# Power.net
KiCad netlist of a schematic drawn in Altium Designer
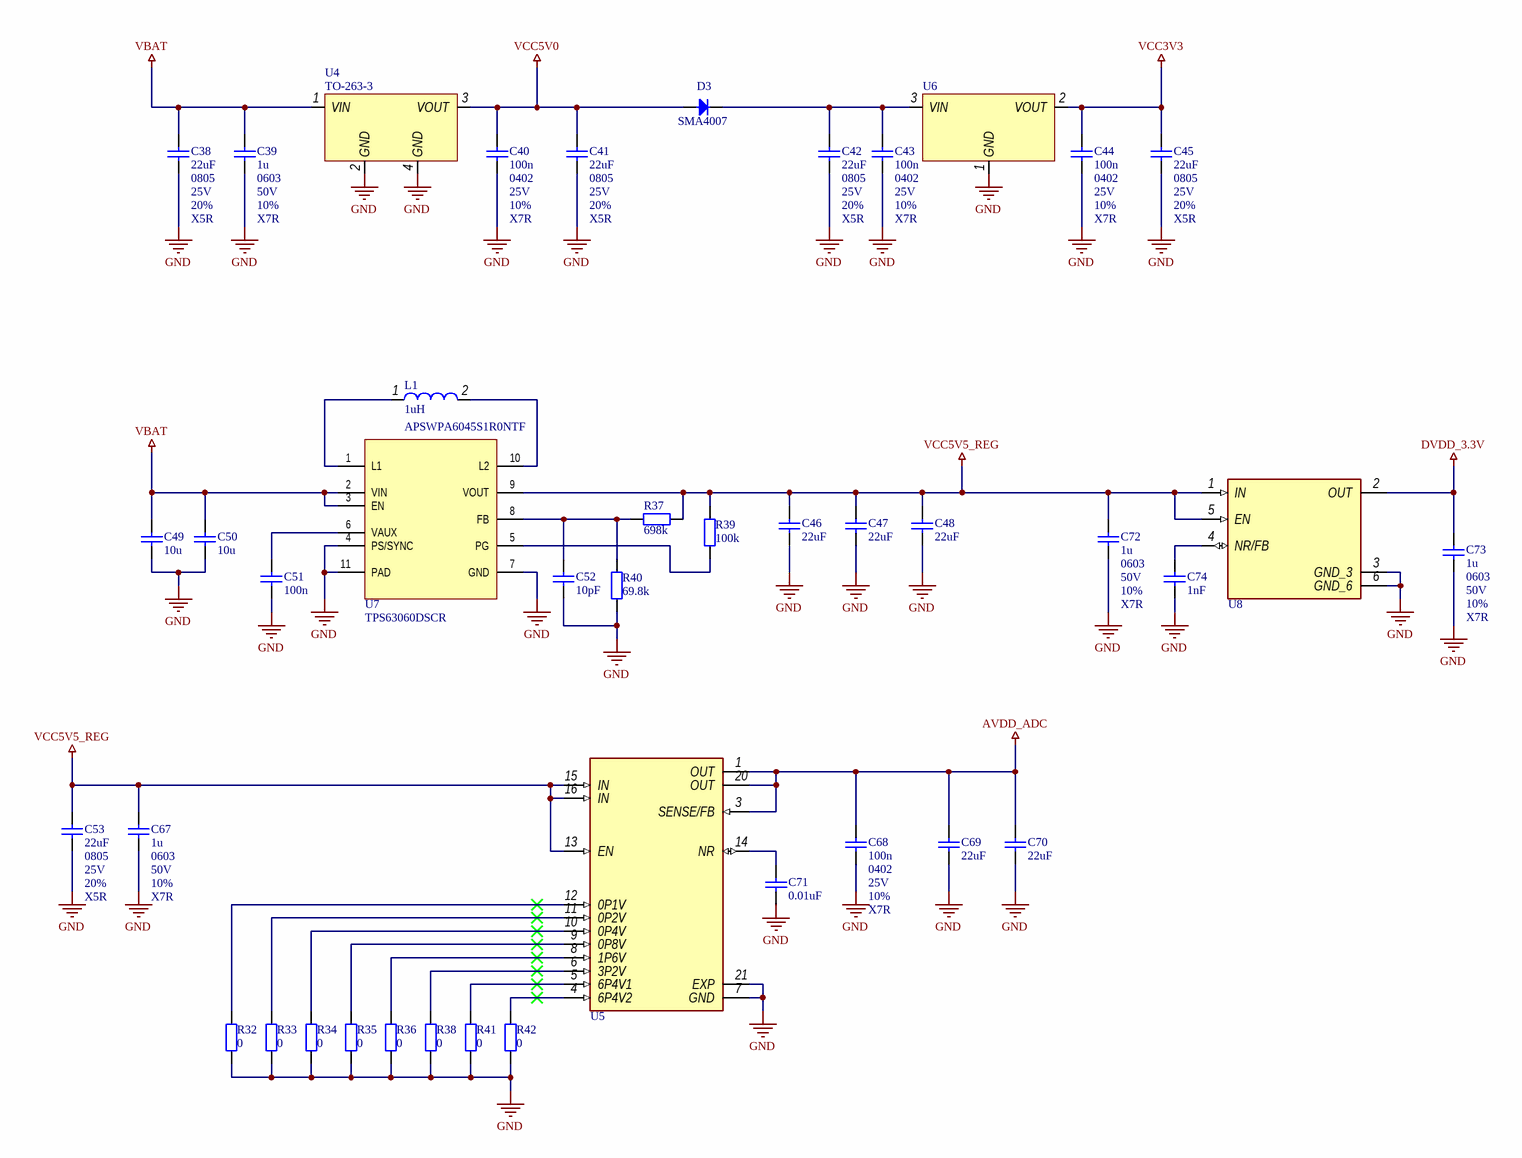
[diagram p0: Power.SchDoc]

(export (version "E")
  (design (tool "Eeschema 10.0.6"))
  (components
    (comp (ref "C38")
      (value "22uF")
      (footprint "CAPC2012X135N")
      (description "CAP CER 0805 22uF 25V X5R")
      (fields
        (field (name "PART NUMBER") "GRM21BR61E226ME44L")
        (field (name "DEVICE") "0805")
        (field (name "VOLTAGE") "25V")
        (field (name "TOLERANCE") "20%")
        (field (name "DIELECTRIC TYPE") "X5R")
        (field (name "MANUFACTURER") "Murata")
        (field (name "AUTHOR") "Arshanitsa D.")
      )
      (libsource (lib "tgl_lib_altium") (part "Capacitor - non polarized"))
    )
    (comp (ref "C39")
      (value "1u")
      (footprint "CAPC1608X85N")
      (description "CAP CER 0603 1u 50V X7R")
      (fields
        (field (name "PART NUMBER") "CC0603KRX7R9BB105")
        (field (name "DEVICE") "0603")
        (field (name "VOLTAGE") "50V")
        (field (name "TOLERANCE") "10%")
        (field (name "DIELECTRIC TYPE") "X7R")
        (field (name "MANUFACTURER") "Yageo")
        (field (name "AUTHOR") "Krepak V.")
      )
      (libsource (lib "tgl_lib_altium") (part "Capacitor - non polarized"))
    )
    (comp (ref "C40")
      (value "100n")
      (footprint "CAPC1005X55N")
      (description "CAP CER 0402 100n 25V X7R")
      (fields
        (field (name "PART NUMBER") "GRM155R71E104KE14D")
        (field (name "DEVICE") "0402")
        (field (name "VOLTAGE") "25V")
        (field (name "TOLERANCE") "10%")
        (field (name "DIELECTRIC TYPE") "X7R")
        (field (name "MANUFACTURER") "Murata")
        (field (name "AUTHOR") "Krepak V.")
      )
      (libsource (lib "tgl_lib_altium") (part "Capacitor - non polarized"))
    )
    (comp (ref "C41")
      (value "22uF")
      (footprint "CAPC2012X135N")
      (description "CAP CER 0805 22uF 25V X5R")
      (fields
        (field (name "PART NUMBER") "GRM21BR61E226ME44L")
        (field (name "DEVICE") "0805")
        (field (name "VOLTAGE") "25V")
        (field (name "TOLERANCE") "20%")
        (field (name "DIELECTRIC TYPE") "X5R")
        (field (name "MANUFACTURER") "Murata")
        (field (name "AUTHOR") "Arshanitsa D.")
      )
      (libsource (lib "tgl_lib_altium") (part "Capacitor - non polarized"))
    )
    (comp (ref "C42")
      (value "22uF")
      (footprint "CAPC2012X135N")
      (description "CAP CER 0805 22uF 25V X5R")
      (fields
        (field (name "PART NUMBER") "GRM21BR61E226ME44L")
        (field (name "DEVICE") "0805")
        (field (name "VOLTAGE") "25V")
        (field (name "TOLERANCE") "20%")
        (field (name "DIELECTRIC TYPE") "X5R")
        (field (name "MANUFACTURER") "Murata")
        (field (name "AUTHOR") "Arshanitsa D.")
      )
      (libsource (lib "tgl_lib_altium") (part "Capacitor - non polarized"))
    )
    (comp (ref "C43")
      (value "100n")
      (footprint "CAPC1005X55N")
      (description "CAP CER 0402 100n 25V X7R")
      (fields
        (field (name "PART NUMBER") "GRM155R71E104KE14D")
        (field (name "DEVICE") "0402")
        (field (name "VOLTAGE") "25V")
        (field (name "TOLERANCE") "10%")
        (field (name "DIELECTRIC TYPE") "X7R")
        (field (name "MANUFACTURER") "Murata")
        (field (name "AUTHOR") "Krepak V.")
      )
      (libsource (lib "tgl_lib_altium") (part "Capacitor - non polarized"))
    )
    (comp (ref "C44")
      (value "100n")
      (footprint "CAPC1005X55N")
      (description "CAP CER 0402 100n 25V X7R")
      (fields
        (field (name "PART NUMBER") "GRM155R71E104KE14D")
        (field (name "DEVICE") "0402")
        (field (name "VOLTAGE") "25V")
        (field (name "TOLERANCE") "10%")
        (field (name "DIELECTRIC TYPE") "X7R")
        (field (name "MANUFACTURER") "Murata")
        (field (name "AUTHOR") "Krepak V.")
      )
      (libsource (lib "tgl_lib_altium") (part "Capacitor - non polarized"))
    )
    (comp (ref "C45")
      (value "22uF")
      (footprint "CAPC2012X135N")
      (description "CAP CER 0805 22uF 25V X5R")
      (fields
        (field (name "PART NUMBER") "GRM21BR61E226ME44L")
        (field (name "DEVICE") "0805")
        (field (name "VOLTAGE") "25V")
        (field (name "TOLERANCE") "20%")
        (field (name "DIELECTRIC TYPE") "X5R")
        (field (name "MANUFACTURER") "Murata")
        (field (name "AUTHOR") "Arshanitsa D.")
      )
      (libsource (lib "tgl_lib_altium") (part "Capacitor - non polarized"))
    )
    (comp (ref "C46")
      (value "22uF")
      (footprint "CAPC2012X135N")
      (description "CAP CER 0805 22uF 25V X5R")
      (fields
        (field (name "PART NUMBER") "GRM21BR61E226ME44L")
        (field (name "VOLTAGE") "25V")
        (field (name "AUTHOR") "Arshanitsa D.")
      )
      (libsource (lib "tgl_lib_altium") (part "Capacitor - non polarized"))
    )
    (comp (ref "C47")
      (value "22uF")
      (footprint "CAPC2012X135N")
      (description "CAP CER 0805 22uF 25V X5R")
      (fields
        (field (name "PART NUMBER") "GRM21BR61E226ME44L")
        (field (name "VOLTAGE") "25V")
        (field (name "AUTHOR") "Arshanitsa D.")
      )
      (libsource (lib "tgl_lib_altium") (part "Capacitor - non polarized"))
    )
    (comp (ref "C48")
      (value "22uF")
      (footprint "CAPC2012X135N")
      (description "CAP CER 0805 22uF 25V X5R")
      (fields
        (field (name "PART NUMBER") "GRM21BR61E226ME44L")
        (field (name "VOLTAGE") "25V")
        (field (name "AUTHOR") "Arshanitsa D.")
      )
      (libsource (lib "tgl_lib_altium") (part "Capacitor - non polarized"))
    )
    (comp (ref "C49")
      (value "10u")
      (footprint "CAPC2012X135N")
      (description "CAP CER 0805 10u 25V X7R")
      (fields
        (field (name "PART NUMBER") "GRM21BZ71E106KE15L")
        (field (name "VOLTAGE") "25V")
        (field (name "AUTHOR") "Krepak V.")
      )
      (libsource (lib "tgl_lib_altium") (part "Capacitor - non polarized"))
    )
    (comp (ref "C50")
      (value "10u")
      (footprint "CAPC2012X135N")
      (description "CAP CER 0805 10u 25V X7R")
      (fields
        (field (name "PART NUMBER") "GRM21BZ71E106KE15L")
        (field (name "VOLTAGE") "25V")
        (field (name "AUTHOR") "Krepak V.")
      )
      (libsource (lib "tgl_lib_altium") (part "Capacitor - non polarized"))
    )
    (comp (ref "C51")
      (value "100n")
      (footprint "CAPC1005X55N")
      (description "CAP CER 0402 100n 25V X7R")
      (fields
        (field (name "PART NUMBER") "GRM155R71E104KE14D")
        (field (name "VOLTAGE") "25V")
        (field (name "AUTHOR") "Krepak V.")
      )
      (libsource (lib "tgl_lib_altium") (part "Capacitor - non polarized"))
    )
    (comp (ref "C52")
      (value "10pF")
      (footprint "CAPC1005X55N")
      (description "CAP CER 0402 10pF 50V NP0")
      (fields
        (field (name "PART NUMBER") "CC0402JRNPO9BN100")
        (field (name "VOLTAGE") "50V")
        (field (name "AUTHOR") "Krepak V.")
      )
      (libsource (lib "tgl_lib_altium") (part "Capacitor - non polarized"))
    )
    (comp (ref "C53")
      (value "22uF")
      (footprint "CAPC2012X135N")
      (description "CAP CER 0805 22uF 25V X5R")
      (fields
        (field (name "PART NUMBER") "GRM21BR61E226ME44L")
        (field (name "DEVICE") "0805")
        (field (name "VOLTAGE") "25V")
        (field (name "TOLERANCE") "20%")
        (field (name "DIELECTRIC TYPE") "X5R")
        (field (name "MANUFACTURER") "Murata")
        (field (name "AUTHOR") "Arshanitsa D.")
      )
      (libsource (lib "tgl_lib_altium") (part "Capacitor - non polarized"))
    )
    (comp (ref "C67")
      (value "1u")
      (footprint "CAPC1608X85N")
      (description "CAP CER 0603 1u 50V X7R")
      (fields
        (field (name "PART NUMBER") "CC0603KRX7R9BB105")
        (field (name "DEVICE") "0603")
        (field (name "VOLTAGE") "50V")
        (field (name "TOLERANCE") "10%")
        (field (name "DIELECTRIC TYPE") "X7R")
        (field (name "MANUFACTURER") "Yageo")
        (field (name "AUTHOR") "Krepak V.")
      )
      (libsource (lib "tgl_lib_altium") (part "Capacitor - non polarized"))
    )
    (comp (ref "C68")
      (value "100n")
      (footprint "CAPC1005X55N")
      (description "CAP CER 0402 100n 25V X7R")
      (fields
        (field (name "PART NUMBER") "GRM155R71E104KE14D")
        (field (name "DEVICE") "0402")
        (field (name "VOLTAGE") "25V")
        (field (name "TOLERANCE") "10%")
        (field (name "DIELECTRIC TYPE") "X7R")
        (field (name "MANUFACTURER") "Murata")
        (field (name "AUTHOR") "Krepak V.")
      )
      (libsource (lib "tgl_lib_altium") (part "Capacitor - non polarized"))
    )
    (comp (ref "C69")
      (value "22uF")
      (footprint "CAPC2012X135N")
      (description "CAP CER 0805 22uF 25V X5R")
      (fields
        (field (name "PART NUMBER") "GRM21BR61E226ME44L")
        (field (name "VOLTAGE") "25V")
        (field (name "AUTHOR") "Arshanitsa D.")
      )
      (libsource (lib "tgl_lib_altium") (part "Capacitor - non polarized"))
    )
    (comp (ref "C70")
      (value "22uF")
      (footprint "CAPC2012X135N")
      (description "CAP CER 0805 22uF 25V X5R")
      (fields
        (field (name "PART NUMBER") "GRM21BR61E226ME44L")
        (field (name "VOLTAGE") "25V")
        (field (name "AUTHOR") "Arshanitsa D.")
      )
      (libsource (lib "tgl_lib_altium") (part "Capacitor - non polarized"))
    )
    (comp (ref "C71")
      (value "0.01uF")
      (footprint "CAPC1005X55N")
      (description "CAP CER 0402 0.01uF 25V X7R")
      (fields
        (field (name "PART NUMBER") "CC0402KRX7R8BB103")
        (field (name "VOLTAGE") "25V")
        (field (name "AUTHOR") "Krepak V.")
      )
      (libsource (lib "tgl_lib_altium") (part "Capacitor - non polarized"))
    )
    (comp (ref "C72")
      (value "1u")
      (footprint "CAPC1608X85N")
      (description "CAP CER 0603 1u 50V X7R")
      (fields
        (field (name "PART NUMBER") "CC0603KRX7R9BB105")
        (field (name "DEVICE") "0603")
        (field (name "VOLTAGE") "50V")
        (field (name "TOLERANCE") "10%")
        (field (name "DIELECTRIC TYPE") "X7R")
        (field (name "MANUFACTURER") "Yageo")
        (field (name "AUTHOR") "Krepak V.")
      )
      (libsource (lib "tgl_lib_altium") (part "Capacitor - non polarized"))
    )
    (comp (ref "C73")
      (value "1u")
      (footprint "CAPC1608X85N")
      (description "CAP CER 0603 1u 50V X7R")
      (fields
        (field (name "PART NUMBER") "CC0603KRX7R9BB105")
        (field (name "DEVICE") "0603")
        (field (name "VOLTAGE") "50V")
        (field (name "TOLERANCE") "10%")
        (field (name "DIELECTRIC TYPE") "X7R")
        (field (name "MANUFACTURER") "Yageo")
        (field (name "AUTHOR") "Krepak V.")
      )
      (libsource (lib "tgl_lib_altium") (part "Capacitor - non polarized"))
    )
    (comp (ref "C74")
      (value "1nF")
      (footprint "CAPC1005X55N")
      (description "CAP CER 0402 1nF 50V NP0")
      (fields
        (field (name "PART NUMBER") "C1005C0G1H102JT000F")
        (field (name "VOLTAGE") "50V")
        (field (name "AUTHOR") "Krepak V.")
      )
      (libsource (lib "tgl_lib_altium") (part "Capacitor - non polarized"))
    )
    (comp (ref "D3")
      (value "SMA4007")
      (footprint "DO-214AC")
      (description "DIODE SMA4007")
      (fields (field (name "MANUFACTURER") "Wing Shing") (field (name "AUTHOR") "Krepak V."))
      (libsource (lib "tgl_lib_altium") (part "Diode"))
    )
    (comp (ref "L1")
      (value "1uH")
      (footprint "APSWPA6045")
      (description "IND APSWPA6045S1R0NTF 1uH ±30%")
      (fields
        (field (name "PART NUMBER") "APSWPA6045S1R0NTF")
        (field (name "TOLERANCE") "±30%")
        (field (name "MANUFACTURER") "APV")
        (field (name "AUTHOR") "Krepak V.")
      )
      (libsource (lib "tgl_lib_altium") (part "Ind"))
    )
    (comp (ref "R32")
      (value "0")
      (footprint "RESC1608X50N")
      (description "RES 0603 0 5%")
      (fields
        (field (name "PART NUMBER") "RC0603JR-070RL")
        (field (name "TOLERANCE") "5%")
        (field (name "AUTHOR") "Arshanitsa D.")
      )
      (libsource (lib "tgl_lib_altium") (part "Resistor1"))
    )
    (comp (ref "R33")
      (value "0")
      (footprint "RESC1608X50N")
      (description "RES 0603 0 5%")
      (fields
        (field (name "PART NUMBER") "RC0603JR-070RL")
        (field (name "TOLERANCE") "5%")
        (field (name "AUTHOR") "Arshanitsa D.")
      )
      (libsource (lib "tgl_lib_altium") (part "Resistor1"))
    )
    (comp (ref "R34")
      (value "0")
      (footprint "RESC1608X50N")
      (description "RES 0603 0 5%")
      (fields
        (field (name "PART NUMBER") "RC0603JR-070RL")
        (field (name "TOLERANCE") "5%")
        (field (name "AUTHOR") "Arshanitsa D.")
      )
      (libsource (lib "tgl_lib_altium") (part "Resistor1"))
    )
    (comp (ref "R35")
      (value "0")
      (footprint "RESC1608X50N")
      (description "RES 0603 0 5%")
      (fields
        (field (name "PART NUMBER") "RC0603JR-070RL")
        (field (name "TOLERANCE") "5%")
        (field (name "AUTHOR") "Arshanitsa D.")
      )
      (libsource (lib "tgl_lib_altium") (part "Resistor1"))
    )
    (comp (ref "R36")
      (value "0")
      (footprint "RESC1608X50N")
      (description "RES 0603 0 5%")
      (fields
        (field (name "PART NUMBER") "RC0603JR-070RL")
        (field (name "TOLERANCE") "5%")
        (field (name "AUTHOR") "Arshanitsa D.")
      )
      (libsource (lib "tgl_lib_altium") (part "Resistor1"))
    )
    (comp (ref "R37")
      (value "698k")
      (footprint "RESC1005X40N")
      (description "RES 0402 698k 1%")
      (fields
        (field (name "PART NUMBER") "RC0402FR-07698KL")
        (field (name "TOLERANCE") "1%")
        (field (name "AUTHOR") "Krepak V.")
      )
      (libsource (lib "") (part "Resistor1_1"))
    )
    (comp (ref "R38")
      (value "0")
      (footprint "RESC1608X50N")
      (description "RES 0603 0 5%")
      (fields
        (field (name "PART NUMBER") "RC0603JR-070RL")
        (field (name "TOLERANCE") "5%")
        (field (name "AUTHOR") "Arshanitsa D.")
      )
      (libsource (lib "tgl_lib_altium") (part "Resistor1"))
    )
    (comp (ref "R39")
      (value "100k")
      (footprint "RESC1005X40N")
      (description "RES 0402 100k 1%")
      (fields
        (field (name "PART NUMBER") "RC0402FR-07100KL")
        (field (name "TOLERANCE") "1%")
        (field (name "AUTHOR") "Krepak V.")
      )
      (libsource (lib "tgl_lib_altium") (part "Resistor1"))
    )
    (comp (ref "R40")
      (value "69.8k")
      (footprint "RESC1005X40N")
      (description "RES 0402 69.8k 1%")
      (fields
        (field (name "PART NUMBER") "RC0402FR-0769K8L")
        (field (name "TOLERANCE") "1%")
        (field (name "AUTHOR") "Krepak V.")
      )
      (libsource (lib "tgl_lib_altium") (part "Resistor1"))
    )
    (comp (ref "R41")
      (value "0")
      (footprint "RESC1608X50N")
      (description "RES 0603 0 5%")
      (fields
        (field (name "PART NUMBER") "RC0603JR-070RL")
        (field (name "TOLERANCE") "5%")
        (field (name "AUTHOR") "Arshanitsa D.")
      )
      (libsource (lib "tgl_lib_altium") (part "Resistor1"))
    )
    (comp (ref "R42")
      (value "0")
      (footprint "RESC1608X50N")
      (description "RES 0603 0 5%")
      (fields
        (field (name "PART NUMBER") "RC0603JR-070RL")
        (field (name "TOLERANCE") "5%")
        (field (name "AUTHOR") "Arshanitsa D.")
      )
      (libsource (lib "tgl_lib_altium") (part "Resistor1"))
    )
    (comp (ref "U4")
      (value "TO-263-3")
      (footprint "TO-263-3_L8.6-W10.2-P2.54-LS14.4-BR")
      (description "TO-263-3 Linear Voltage Regulators (LDO) ROHS")
      (fields
        (field (name "PART NUMBER") "LM7805S/TR")
        (field (name "Comment") "LM7805S")
        (field (name "AUTHOR") "Krepak V.")
      )
      (libsource (lib "tgl_lib_altium") (part "LM7805S"))
    )
    (comp (ref "U5")
      (value "TPS7A4700RGWR")
      (footprint "QFN65P500X500X100-21N")
      (description "1-A, 36-V, low-noise, high-PSRR, low-dropout voltage regulator with enable 20-VQFN -40 to 125")
      (fields (field (name "MF") "Texas Instruments") (field (name "AUTHOR") "Krepak V."))
      (libsource (lib "tgl_lib_altium") (part "TPS7A4700RGWR"))
    )
    (comp (ref "U6")
      (value "AMS1117-3.3")
      (footprint "SOT230P700-4BN")
      (libsource (lib "tgl_lib_altium") (part "AMS1117-3.3"))
    )
    (comp (ref "U7")
      (value "TPS63060DSCR")
      (footprint "WSON10")
      (description "Buck-boost type Adjustable 2.5V~8V 2A 2.5V~12V DFN-10(3x3) DC-DC Converters ROHS")
      (fields (field (name "MANUFACTURER") "Texas Instruments") (field (name "AUTHOR") "Krepak V."))
      (libsource (lib "tgl_lib_altium") (part "TPS63060"))
    )
    (comp (ref "U8")
      (value "TPS73733DCQR")
      (footprint "IC_TPS73733DCQR")
      (fields (field (name "AUTHOR") "Krepak V."))
      (libsource (lib "tgl_lib_altium") (part "TPS73733DCQR"))
    )
  )
  (nets
    (net (code "1") (name "AVDD_ADC") (class "Default")
      (node (ref "C68") (pin "2") (pinfunction "2_2") (pintype "passive"))
      (node (ref "C69") (pin "2") (pinfunction "2_2") (pintype "passive"))
      (node (ref "C70") (pin "2") (pinfunction "2_2") (pintype "passive"))
      (node (ref "U5") (pin "1") (pinfunction "OUT_1") (pintype "power_in"))
      (node (ref "U5") (pin "20") (pinfunction "OUT_20") (pintype "power_in"))
      (node (ref "U5") (pin "3") (pinfunction "SENSE/FB_3") (pintype "input"))
    )
    (net (code "2") (name "DVDD_3.3V") (class "Default")
      (node (ref "C73") (pin "2") (pinfunction "2_2") (pintype "passive"))
      (node (ref "U8") (pin "2") (pinfunction "OUT_2") (pintype "power_in"))
    )
    (net (code "3") (name "GND") (class "Default")
      (node (ref "C38") (pin "1") (pinfunction "1_1") (pintype "passive"))
      (node (ref "C39") (pin "1") (pinfunction "1_1") (pintype "passive"))
      (node (ref "C40") (pin "1") (pinfunction "1_1") (pintype "passive"))
      (node (ref "C41") (pin "1") (pinfunction "1_1") (pintype "passive"))
      (node (ref "C42") (pin "1") (pinfunction "1_1") (pintype "passive"))
      (node (ref "C43") (pin "1") (pinfunction "1_1") (pintype "passive"))
      (node (ref "C44") (pin "1") (pinfunction "1_1") (pintype "passive"))
      (node (ref "C45") (pin "1") (pinfunction "1_1") (pintype "passive"))
      (node (ref "C46") (pin "1") (pinfunction "1_1") (pintype "passive"))
      (node (ref "C47") (pin "1") (pinfunction "1_1") (pintype "passive"))
      (node (ref "C48") (pin "1") (pinfunction "1_1") (pintype "passive"))
      (node (ref "C49") (pin "1") (pinfunction "1_1") (pintype "passive"))
      (node (ref "C50") (pin "1") (pinfunction "1_1") (pintype "passive"))
      (node (ref "C51") (pin "1") (pinfunction "1_1") (pintype "passive"))
      (node (ref "C52") (pin "1") (pinfunction "1_1") (pintype "passive"))
      (node (ref "C53") (pin "1") (pinfunction "1_1") (pintype "passive"))
      (node (ref "C67") (pin "1") (pinfunction "1_1") (pintype "passive"))
      (node (ref "C68") (pin "1") (pinfunction "1_1") (pintype "passive"))
      (node (ref "C69") (pin "1") (pinfunction "1_1") (pintype "passive"))
      (node (ref "C70") (pin "1") (pinfunction "1_1") (pintype "passive"))
      (node (ref "C71") (pin "1") (pinfunction "1_1") (pintype "passive"))
      (node (ref "C72") (pin "1") (pinfunction "1_1") (pintype "passive"))
      (node (ref "C73") (pin "1") (pinfunction "1_1") (pintype "passive"))
      (node (ref "C74") (pin "1") (pinfunction "1_1") (pintype "passive"))
      (node (ref "R32") (pin "1") (pinfunction "1_1") (pintype "passive"))
      (node (ref "R33") (pin "1") (pinfunction "1_1") (pintype "passive"))
      (node (ref "R34") (pin "1") (pinfunction "1_1") (pintype "passive"))
      (node (ref "R35") (pin "1") (pinfunction "1_1") (pintype "passive"))
      (node (ref "R36") (pin "1") (pinfunction "1_1") (pintype "passive"))
      (node (ref "R38") (pin "1") (pinfunction "1_1") (pintype "passive"))
      (node (ref "R40") (pin "1") (pinfunction "1_1") (pintype "passive"))
      (node (ref "R41") (pin "1") (pinfunction "1_1") (pintype "passive"))
      (node (ref "R42") (pin "1") (pinfunction "1_1") (pintype "passive"))
      (node (ref "U4") (pin "2") (pinfunction "GND_2") (pintype "power_in"))
      (node (ref "U4") (pin "4") (pinfunction "GND_4") (pintype "power_in"))
      (node (ref "U5") (pin "21") (pinfunction "EXP_21") (pintype "power_in"))
      (node (ref "U5") (pin "7") (pinfunction "GND_7") (pintype "power_in"))
      (node (ref "U6") (pin "1") (pinfunction "GND_1") (pintype "power_in"))
      (node (ref "U7") (pin "11") (pinfunction "PAD_11") (pintype "power_in"))
      (node (ref "U7") (pin "4") (pinfunction "PS/SYNC_4") (pintype "passive"))
      (node (ref "U7") (pin "7") (pinfunction "GND_7") (pintype "power_in"))
      (node (ref "U8") (pin "3") (pinfunction "GND_3_3") (pintype "power_in"))
      (node (ref "U8") (pin "6") (pinfunction "GND_6_6") (pintype "power_in"))
    )
    (net (code "4") (name "Net-(D3-C)") (class "Default")
      (node (ref "C42") (pin "2") (pinfunction "2_2") (pintype "passive"))
      (node (ref "C43") (pin "2") (pinfunction "2_2") (pintype "passive"))
      (node (ref "D3") (pin "2") (pinfunction "C_2") (pintype "passive"))
      (node (ref "U6") (pin "3") (pinfunction "VIN_3") (pintype "power_in"))
    )
    (net (code "5") (name "Net-(U5-0P1V)") (class "Default")
      (node (ref "R32") (pin "2") (pinfunction "2_2") (pintype "passive"))
      (node (ref "U5") (pin "12") (pinfunction "0P1V_12") (pintype "input"))
    )
    (net (code "6") (name "Net-(U5-0P2V)") (class "Default")
      (node (ref "R33") (pin "2") (pinfunction "2_2") (pintype "passive"))
      (node (ref "U5") (pin "11") (pinfunction "0P2V_11") (pintype "input"))
    )
    (net (code "7") (name "Net-(U5-0P4V)") (class "Default")
      (node (ref "R34") (pin "2") (pinfunction "2_2") (pintype "passive"))
      (node (ref "U5") (pin "10") (pinfunction "0P4V_10") (pintype "input"))
    )
    (net (code "8") (name "Net-(U5-0P8V)") (class "Default")
      (node (ref "R35") (pin "2") (pinfunction "2_2") (pintype "passive"))
      (node (ref "U5") (pin "9") (pinfunction "0P8V_9") (pintype "input"))
    )
    (net (code "9") (name "Net-(U5-1P6V)") (class "Default")
      (node (ref "R36") (pin "2") (pinfunction "2_2") (pintype "passive"))
      (node (ref "U5") (pin "8") (pinfunction "1P6V_8") (pintype "input"))
    )
    (net (code "10") (name "Net-(U5-3P2V)") (class "Default")
      (node (ref "R38") (pin "2") (pinfunction "2_2") (pintype "passive"))
      (node (ref "U5") (pin "6") (pinfunction "3P2V_6") (pintype "input"))
    )
    (net (code "11") (name "Net-(U5-6P4V1)") (class "Default")
      (node (ref "R41") (pin "2") (pinfunction "2_2") (pintype "passive"))
      (node (ref "U5") (pin "5") (pinfunction "6P4V1_5") (pintype "input"))
    )
    (net (code "12") (name "Net-(U5-6P4V2)") (class "Default")
      (node (ref "R42") (pin "2") (pinfunction "2_2") (pintype "passive"))
      (node (ref "U5") (pin "4") (pinfunction "6P4V2_4") (pintype "input"))
    )
    (net (code "13") (name "Net-(U5-NR)") (class "Default")
      (node (ref "C71") (pin "2") (pinfunction "2_2") (pintype "passive"))
      (node (ref "U5") (pin "14") (pinfunction "NR_14") (pintype "bidirectional"))
    )
    (net (code "14") (name "Net-(U7-FB)") (class "Default")
      (node (ref "C52") (pin "2") (pinfunction "2_2") (pintype "passive"))
      (node (ref "R37") (pin "1") (pinfunction "1_1") (pintype "passive"))
      (node (ref "R40") (pin "2") (pinfunction "2_2") (pintype "passive"))
      (node (ref "U7") (pin "8") (pinfunction "FB_8") (pintype "power_in"))
    )
    (net (code "15") (name "Net-(U7-L1)") (class "Default")
      (node (ref "L1") (pin "1") (pinfunction "1_1") (pintype "passive"))
      (node (ref "U7") (pin "1") (pinfunction "L1_1") (pintype "passive"))
    )
    (net (code "16") (name "Net-(U7-L2)") (class "Default")
      (node (ref "L1") (pin "2") (pinfunction "2_2") (pintype "passive"))
      (node (ref "U7") (pin "10") (pinfunction "L2_10") (pintype "passive"))
    )
    (net (code "17") (name "Net-(U7-PG)") (class "Default")
      (node (ref "R39") (pin "1") (pinfunction "1_1") (pintype "passive"))
      (node (ref "U7") (pin "5") (pinfunction "PG_5") (pintype "passive"))
    )
    (net (code "18") (name "Net-(U7-VAUX)") (class "Default")
      (node (ref "C51") (pin "2") (pinfunction "2_2") (pintype "passive"))
      (node (ref "U7") (pin "6") (pinfunction "VAUX_6") (pintype "passive"))
    )
    (net (code "19") (name "Net-(U8-NR{slash}FB)") (class "Default")
      (node (ref "C74") (pin "2") (pinfunction "2_2") (pintype "passive"))
      (node (ref "U8") (pin "4") (pinfunction "NR/FB_4") (pintype "bidirectional"))
    )
    (net (code "20") (name "VBAT") (class "Default")
      (node (ref "C38") (pin "2") (pinfunction "2_2") (pintype "passive"))
      (node (ref "C39") (pin "2") (pinfunction "2_2") (pintype "passive"))
      (node (ref "C49") (pin "2") (pinfunction "2_2") (pintype "passive"))
      (node (ref "C50") (pin "2") (pinfunction "2_2") (pintype "passive"))
      (node (ref "U4") (pin "1") (pinfunction "VIN_1") (pintype "power_in"))
      (node (ref "U7") (pin "2") (pinfunction "VIN_2") (pintype "passive"))
      (node (ref "U7") (pin "3") (pinfunction "EN_3") (pintype "passive"))
    )
    (net (code "21") (name "VCC3V3") (class "Default")
      (node (ref "C44") (pin "2") (pinfunction "2_2") (pintype "passive"))
      (node (ref "C45") (pin "2") (pinfunction "2_2") (pintype "passive"))
      (node (ref "U6") (pin "2") (pinfunction "VOUT_2") (pintype "power_in"))
    )
    (net (code "22") (name "VCC5V0") (class "Default")
      (node (ref "C40") (pin "2") (pinfunction "2_2") (pintype "passive"))
      (node (ref "C41") (pin "2") (pinfunction "2_2") (pintype "passive"))
      (node (ref "D3") (pin "1") (pinfunction "A_1") (pintype "passive"))
      (node (ref "U4") (pin "3") (pinfunction "VOUT_3") (pintype "power_in"))
    )
    (net (code "23") (name "VCC5V5_REG") (class "Default")
      (node (ref "C46") (pin "2") (pinfunction "2_2") (pintype "passive"))
      (node (ref "C47") (pin "2") (pinfunction "2_2") (pintype "passive"))
      (node (ref "C48") (pin "2") (pinfunction "2_2") (pintype "passive"))
      (node (ref "C53") (pin "2") (pinfunction "2_2") (pintype "passive"))
      (node (ref "C67") (pin "2") (pinfunction "2_2") (pintype "passive"))
      (node (ref "C72") (pin "2") (pinfunction "2_2") (pintype "passive"))
      (node (ref "R37") (pin "2") (pinfunction "2_2") (pintype "passive"))
      (node (ref "R39") (pin "2") (pinfunction "2_2") (pintype "passive"))
      (node (ref "U5") (pin "13") (pinfunction "EN_13") (pintype "input"))
      (node (ref "U5") (pin "15") (pinfunction "IN_15") (pintype "input"))
      (node (ref "U5") (pin "16") (pinfunction "IN_16") (pintype "input"))
      (node (ref "U7") (pin "9") (pinfunction "VOUT_9") (pintype "power_in"))
      (node (ref "U8") (pin "1") (pinfunction "IN_1") (pintype "input"))
      (node (ref "U8") (pin "5") (pinfunction "EN_5") (pintype "input"))
    )
  )
)
